# FiveLEDsPuzzle.net
KiCad netlist of a schematic drawn in EAGLE
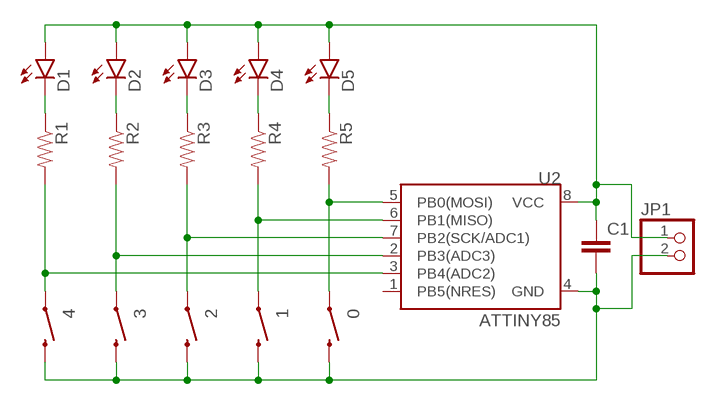
[diagram p0: schematic, sheet 1]

(export (version "E")
  (design (tool "Eeschema 10.0.6"))
  (components
    (comp (ref "0")
      (value "SWITCH-MOMENTARY-2PTH")
      (footprint "eagle-import:TACTILE-PTH")
      (libsource (lib "eagle-import") (part "SWITCH-MOMENTARY-2PTH"))
    )
    (comp (ref "1")
      (value "SWITCH-MOMENTARY-2PTH")
      (footprint "eagle-import:TACTILE-PTH")
      (libsource (lib "eagle-import") (part "SWITCH-MOMENTARY-2PTH"))
    )
    (comp (ref "2")
      (value "SWITCH-MOMENTARY-2PTH")
      (footprint "eagle-import:TACTILE-PTH")
      (libsource (lib "eagle-import") (part "SWITCH-MOMENTARY-2PTH"))
    )
    (comp (ref "3")
      (value "SWITCH-MOMENTARY-2PTH")
      (footprint "eagle-import:TACTILE-PTH")
      (libsource (lib "eagle-import") (part "SWITCH-MOMENTARY-2PTH"))
    )
    (comp (ref "4")
      (value "SWITCH-MOMENTARY-2PTH")
      (footprint "eagle-import:TACTILE-PTH")
      (libsource (lib "eagle-import") (part "SWITCH-MOMENTARY-2PTH"))
    )
    (comp (ref "C1")
      (value "0.1UF-50V-20%(PTH)KIT-EZ")
      (footprint "eagle-import:CAP-PTH-SMALL-KIT")
      (libsource (lib "eagle-import") (part "0.1UF-50V-20%(PTH)KIT-EZ"))
    )
    (comp (ref "D1")
      (value "LED5MM")
      (footprint "eagle-import:LED5MM")
      (libsource (lib "eagle-import") (part "LED5MM"))
    )
    (comp (ref "D2")
      (value "LED5MM")
      (footprint "eagle-import:LED5MM")
      (libsource (lib "eagle-import") (part "LED5MM"))
    )
    (comp (ref "D3")
      (value "LED5MM")
      (footprint "eagle-import:LED5MM")
      (libsource (lib "eagle-import") (part "LED5MM"))
    )
    (comp (ref "D4")
      (value "LED5MM")
      (footprint "eagle-import:LED5MM")
      (libsource (lib "eagle-import") (part "LED5MM"))
    )
    (comp (ref "D5")
      (value "LED5MM")
      (footprint "eagle-import:LED5MM")
      (libsource (lib "eagle-import") (part "LED5MM"))
    )
    (comp (ref "JP1")
      (value "HEADER-1X2ROUND")
      (footprint "eagle-import:1X02_ROUND")
      (libsource (lib "eagle-import") (part "HEADER-1X2ROUND"))
    )
    (comp (ref "R1")
      (value "RESISTORAXIAL-0.3")
      (footprint "eagle-import:AXIAL-0.3")
      (libsource (lib "eagle-import") (part "RESISTORAXIAL-0.3"))
    )
    (comp (ref "R2")
      (value "RESISTORAXIAL-0.3")
      (footprint "eagle-import:AXIAL-0.3")
      (libsource (lib "eagle-import") (part "RESISTORAXIAL-0.3"))
    )
    (comp (ref "R3")
      (value "RESISTORAXIAL-0.3")
      (footprint "eagle-import:AXIAL-0.3")
      (libsource (lib "eagle-import") (part "RESISTORAXIAL-0.3"))
    )
    (comp (ref "R4")
      (value "RESISTORAXIAL-0.3")
      (footprint "eagle-import:AXIAL-0.3")
      (libsource (lib "eagle-import") (part "RESISTORAXIAL-0.3"))
    )
    (comp (ref "R5")
      (value "RESISTORAXIAL-0.3")
      (footprint "eagle-import:AXIAL-0.3")
      (libsource (lib "eagle-import") (part "RESISTORAXIAL-0.3"))
    )
    (comp (ref "U2")
      (value "ATTINY85")
      (footprint "eagle-import:DIP08")
      (libsource (lib "eagle-import") (part "ATTINY45TINY85-20-DIP"))
    )
  )
  (nets
    (net (code "1") (name "Net-(0-2)") (class "Default")
      (node (ref "0") (pin "3") (pinfunction "2_3") (pintype "passive"))
      (node (ref "1") (pin "3") (pinfunction "2_3") (pintype "passive"))
      (node (ref "2") (pin "3") (pinfunction "2_3") (pintype "passive"))
      (node (ref "3") (pin "3") (pinfunction "2_3") (pintype "passive"))
      (node (ref "4") (pin "3") (pinfunction "2_3") (pintype "passive"))
      (node (ref "C1") (pin "2") (pinfunction "2_2") (pintype "passive"))
      (node (ref "JP1") (pin "2") (pinfunction "2_2") (pintype "passive"))
      (node (ref "U2") (pin "4") (pinfunction "GND_4") (pintype "bidirectional"))
    )
    (net (code "2") (name "Net-(D1-C)") (class "Default")
      (node (ref "D1") (pin "K") (pinfunction "C_K") (pintype "passive"))
      (node (ref "R1") (pin "P$1") (pinfunction "1_P$1") (pintype "passive"))
    )
    (net (code "3") (name "Net-(D2-C)") (class "Default")
      (node (ref "D2") (pin "K") (pinfunction "C_K") (pintype "passive"))
      (node (ref "R2") (pin "P$1") (pinfunction "1_P$1") (pintype "passive"))
    )
    (net (code "4") (name "Net-(D3-C)") (class "Default")
      (node (ref "D3") (pin "K") (pinfunction "C_K") (pintype "passive"))
      (node (ref "R3") (pin "P$1") (pinfunction "1_P$1") (pintype "passive"))
    )
    (net (code "5") (name "Net-(D4-C)") (class "Default")
      (node (ref "D4") (pin "K") (pinfunction "C_K") (pintype "passive"))
      (node (ref "R4") (pin "P$1") (pinfunction "1_P$1") (pintype "passive"))
    )
    (net (code "6") (name "Net-(D5-C)") (class "Default")
      (node (ref "D5") (pin "K") (pinfunction "C_K") (pintype "passive"))
      (node (ref "R5") (pin "P$1") (pinfunction "1_P$1") (pintype "passive"))
    )
    (net (code "7") (name "Net-(R1-2)") (class "Default")
      (node (ref "4") (pin "1") (pinfunction "1_1") (pintype "passive"))
      (node (ref "R1") (pin "P$2") (pinfunction "2_P$2") (pintype "passive"))
      (node (ref "U2") (pin "3") (pinfunction "PB4(ADC2)_3") (pintype "bidirectional"))
    )
    (net (code "8") (name "Net-(R2-2)") (class "Default")
      (node (ref "3") (pin "1") (pinfunction "1_1") (pintype "passive"))
      (node (ref "R2") (pin "P$2") (pinfunction "2_P$2") (pintype "passive"))
      (node (ref "U2") (pin "2") (pinfunction "PB3(ADC3)_2") (pintype "bidirectional"))
    )
    (net (code "9") (name "Net-(R3-2)") (class "Default")
      (node (ref "2") (pin "1") (pinfunction "1_1") (pintype "passive"))
      (node (ref "R3") (pin "P$2") (pinfunction "2_P$2") (pintype "passive"))
      (node (ref "U2") (pin "7") (pinfunction "PB2(SCK/ADC1)_7") (pintype "bidirectional"))
    )
    (net (code "10") (name "Net-(R4-2)") (class "Default")
      (node (ref "1") (pin "1") (pinfunction "1_1") (pintype "passive"))
      (node (ref "R4") (pin "P$2") (pinfunction "2_P$2") (pintype "passive"))
      (node (ref "U2") (pin "6") (pinfunction "PB1(MISO)_6") (pintype "bidirectional"))
    )
    (net (code "11") (name "Net-(R5-2)") (class "Default")
      (node (ref "0") (pin "1") (pinfunction "1_1") (pintype "passive"))
      (node (ref "R5") (pin "P$2") (pinfunction "2_P$2") (pintype "passive"))
      (node (ref "U2") (pin "5") (pinfunction "PB0(MOSI)_5") (pintype "bidirectional"))
    )
    (net (code "12") (name "Net-(U2-VCC)") (class "Default")
      (node (ref "C1") (pin "1") (pinfunction "1_1") (pintype "passive"))
      (node (ref "D1") (pin "A") (pinfunction "A_A") (pintype "passive"))
      (node (ref "D2") (pin "A") (pinfunction "A_A") (pintype "passive"))
      (node (ref "D3") (pin "A") (pinfunction "A_A") (pintype "passive"))
      (node (ref "D4") (pin "A") (pinfunction "A_A") (pintype "passive"))
      (node (ref "D5") (pin "A") (pinfunction "A_A") (pintype "passive"))
      (node (ref "JP1") (pin "1") (pinfunction "1_1") (pintype "passive"))
      (node (ref "U2") (pin "8") (pinfunction "VCC_8") (pintype "bidirectional"))
    )
    (net (code "13") (name "unconnected-(U2-PB5(NRES)-Pad1)") (class "Default")
      (node (ref "U2") (pin "1") (pinfunction "PB5(NRES)_1") (pintype "bidirectional"))
    )
  )
)
